# Power.net
KiCad netlist of a schematic drawn in Altium Designer
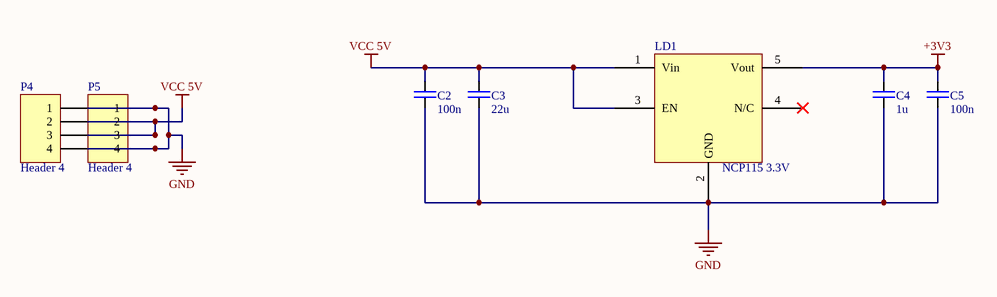
[diagram p0: Power.SchDoc]

(export (version "E")
  (design (tool "Eeschema 10.0.6"))
  (components
    (comp (ref "C2")
      (value "100n")
      (footprint "R1005_0402i_L")
      (description "Capacitor")
      (libsource (lib "General") (part "C"))
    )
    (comp (ref "C3")
      (value "22u")
      (footprint "C1608_0603I_L")
      (description "Capacitor")
      (libsource (lib "General") (part "C"))
    )
    (comp (ref "C4")
      (value "1u")
      (footprint "R1005_0402i_L")
      (description "Capacitor")
      (libsource (lib "General") (part "C"))
    )
    (comp (ref "C5")
      (value "100n")
      (footprint "R1005_0402i_L")
      (description "Capacitor")
      (libsource (lib "General") (part "C"))
    )
    (comp (ref "LD1")
      (value "NCP115 3.3V")
      (footprint "TSOP95P280X110-6L")
      (libsource (lib "components_library") (part "NCP115 3.3V"))
    )
    (comp (ref "P4")
      (value "Header 4")
      (footprint "HDR1X4")
      (description "Header, 4-Pin")
      (fields (field (name "PUBLISHER") "Altium Limited"))
      (libsource (lib "Miscellaneous Connectors") (part "Header 4"))
    )
    (comp (ref "P5")
      (value "Header 4")
      (footprint "HDR1X4")
      (description "Header, 4-Pin")
      (fields (field (name "PUBLISHER") "Altium Limited"))
      (libsource (lib "Miscellaneous Connectors") (part "Header 4"))
    )
  )
  (nets
    (net (code "1") (name "+3V3") (class "Default")
      (node (ref "C4") (pin "1") (pinfunction "1_1") (pintype "passive"))
      (node (ref "C5") (pin "1") (pinfunction "1_1") (pintype "passive"))
      (node (ref "LD1") (pin "5") (pinfunction "Vout_5") (pintype "passive"))
    )
    (net (code "2") (name "GND") (class "Default")
      (node (ref "C2") (pin "2") (pinfunction "2_2") (pintype "passive"))
      (node (ref "C3") (pin "2") (pinfunction "2_2") (pintype "passive"))
      (node (ref "C4") (pin "2") (pinfunction "2_2") (pintype "passive"))
      (node (ref "C5") (pin "2") (pinfunction "2_2") (pintype "passive"))
      (node (ref "LD1") (pin "2") (pinfunction "GND_2") (pintype "passive"))
      (node (ref "P4") (pin "1") (pinfunction "1_1") (pintype "passive"))
      (node (ref "P4") (pin "4") (pinfunction "4_4") (pintype "passive"))
      (node (ref "P5") (pin "1") (pinfunction "1_1") (pintype "passive"))
      (node (ref "P5") (pin "4") (pinfunction "4_4") (pintype "passive"))
    )
    (net (code "3") (name "VCC 5V") (class "Default")
      (node (ref "C2") (pin "1") (pinfunction "1_1") (pintype "passive"))
      (node (ref "C3") (pin "1") (pinfunction "1_1") (pintype "passive"))
      (node (ref "LD1") (pin "1") (pinfunction "Vin_1") (pintype "passive"))
      (node (ref "LD1") (pin "3") (pinfunction "EN_3") (pintype "passive"))
      (node (ref "P4") (pin "2") (pinfunction "2_2") (pintype "passive"))
      (node (ref "P4") (pin "3") (pinfunction "3_3") (pintype "passive"))
      (node (ref "P5") (pin "2") (pinfunction "2_2") (pintype "passive"))
      (node (ref "P5") (pin "3") (pinfunction "3_3") (pintype "passive"))
    )
    (net (code "4") (name "unconnected-(LD1-N{slash}C-Pad4)") (class "Default")
      (node (ref "LD1") (pin "4") (pinfunction "N/C_4") (pintype "passive+no_connect"))
    )
  )
)
